# GrandPrIEEE.net
KiCad netlist of a schematic drawn in EAGLE
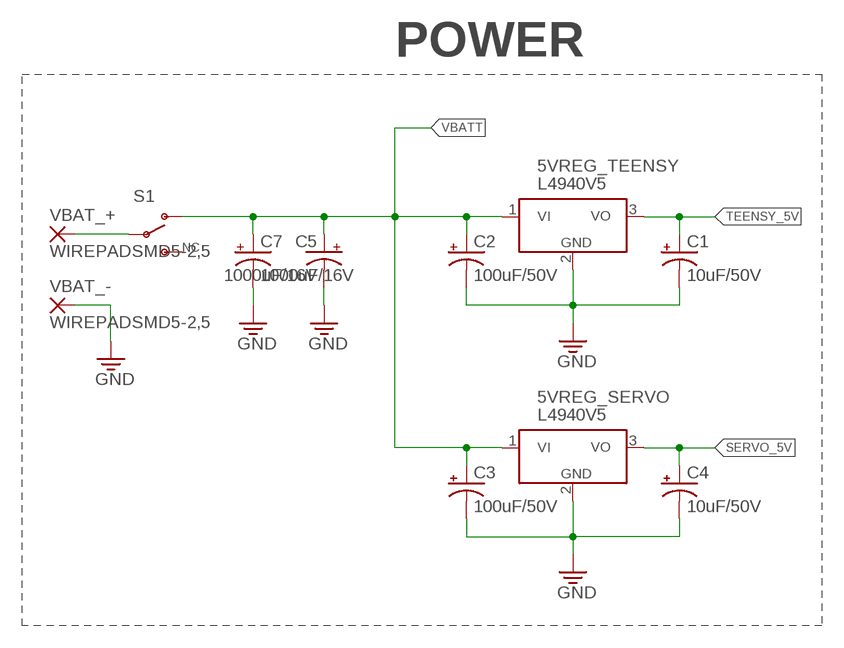
[diagram p0: schematic, sheet 1, part 1 of 2]
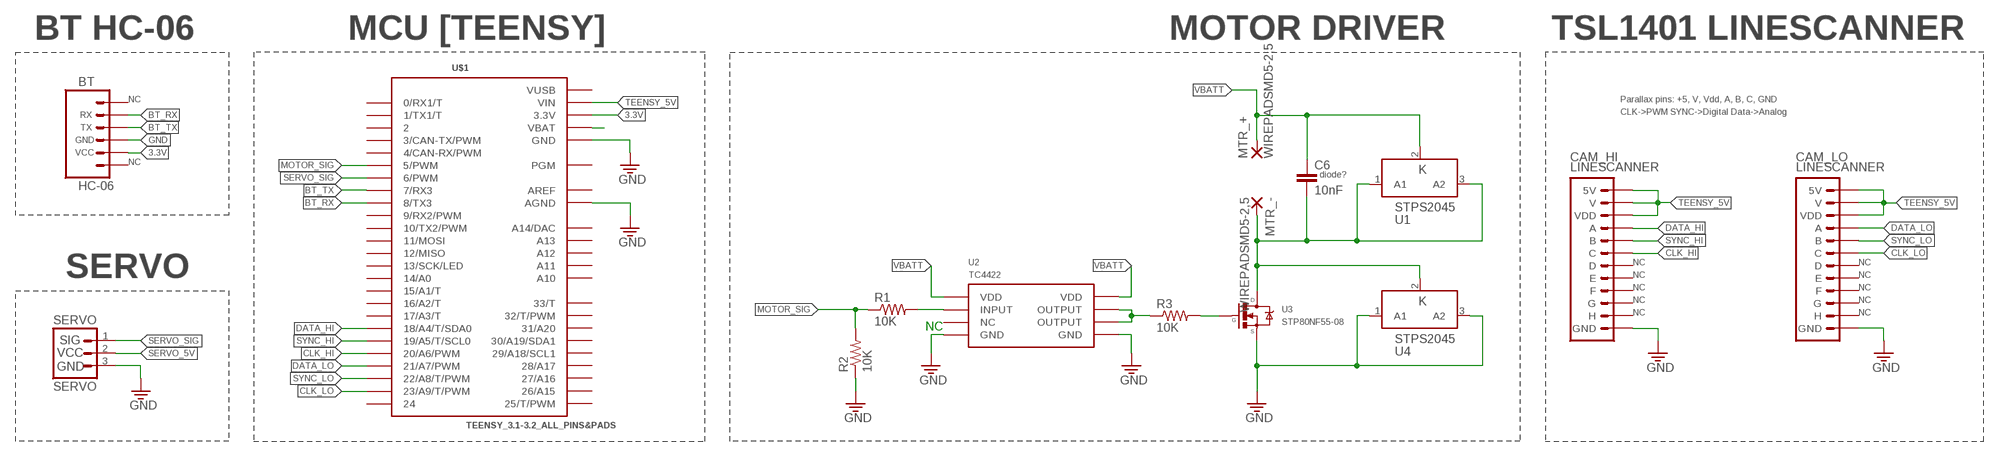
[diagram p1: schematic, sheet 1, part 2 of 2]

(export (version "E")
  (design (tool "Eeschema 10.0.6"))
  (components
    (comp (ref "5VREG_SERVO")
      (value "L4940V5")
      (footprint "eagle-import:TO-220-HEATSINK")
      (libsource (lib "eagle-import") (part "L4940V5_HEATSINK"))
    )
    (comp (ref "5VREG_TEENSY")
      (value "L4940V5")
      (footprint "eagle-import:TO-220-HEATSINK")
      (libsource (lib "eagle-import") (part "L4940V5_HEATSINK"))
    )
    (comp (ref "BT")
      (value "HC-06")
      (footprint "eagle-import:1X06")
      (libsource (lib "eagle-import") (part "HC-06"))
    )
    (comp (ref "C1")
      (value "10uF/50V")
      (footprint "eagle-import:E2,5-5")
      (libsource (lib "eagle-import") (part "CPOL-USE2.5-5"))
    )
    (comp (ref "C2")
      (value "100uF/50V")
      (footprint "eagle-import:E3,5-8")
      (libsource (lib "eagle-import") (part "CPOL-USE3.5-8"))
    )
    (comp (ref "C3")
      (value "100uF/50V")
      (footprint "eagle-import:E3,5-8")
      (libsource (lib "eagle-import") (part "CPOL-USE3.5-8"))
    )
    (comp (ref "C4")
      (value "10uF/50V")
      (footprint "eagle-import:E2,5-5")
      (libsource (lib "eagle-import") (part "CPOL-USE2.5-5"))
    )
    (comp (ref "C5")
      (value "1000uF/16V")
      (footprint "eagle-import:E5-10,5")
      (libsource (lib "eagle-import") (part "CPOL-USE5-10.5"))
    )
    (comp (ref "C6")
      (value "10nF")
      (footprint "eagle-import:C025-025X050")
      (libsource (lib "eagle-import") (part "C-EU025-025X050"))
    )
    (comp (ref "C7")
      (value "1000uF/16V")
      (footprint "eagle-import:E5-10,5")
      (libsource (lib "eagle-import") (part "CPOL-USE5-10.5"))
    )
    (comp (ref "CAM_HI")
      (value "LINESCANNER")
      (footprint "eagle-import:LINESCANNER")
      (libsource (lib "eagle-import") (part "LINESCANNER"))
    )
    (comp (ref "CAM_LO")
      (value "LINESCANNER")
      (footprint "eagle-import:LINESCANNER")
      (libsource (lib "eagle-import") (part "LINESCANNER"))
    )
    (comp (ref "MTR_+")
      (value "WIREPADSMD5-2,5")
      (footprint "eagle-import:5-2,5")
      (libsource (lib "eagle-import") (part "WIREPADSMD5-2,5"))
    )
    (comp (ref "MTR_-")
      (value "WIREPADSMD5-2,5")
      (footprint "eagle-import:5-2,5")
      (libsource (lib "eagle-import") (part "WIREPADSMD5-2,5"))
    )
    (comp (ref "R1")
      (value "10K")
      (footprint "eagle-import:0207_7")
      (libsource (lib "eagle-import") (part "R-US_0207/7"))
    )
    (comp (ref "R2")
      (value "10K")
      (footprint "eagle-import:0207_7")
      (libsource (lib "eagle-import") (part "R-US_0207/7"))
    )
    (comp (ref "R3")
      (value "10K")
      (footprint "eagle-import:0207_7")
      (libsource (lib "eagle-import") (part "R-US_0207/7"))
    )
    (comp (ref "S1")
      (value "SW_MTS-102C4")
      (footprint "eagle-import:MTS-102C4")
      (libsource (lib "eagle-import") (part "SW_MTS-102C4"))
    )
    (comp (ref "SERVO")
      (value "SERVO")
      (footprint "eagle-import:1X03")
      (libsource (lib "eagle-import") (part "SERVO"))
    )
    (comp (ref "U$1")
      (value "TEENSY_3.1-3.2_ALL_PINS&PADS")
      (footprint "eagle-import:TEENSY_3.0-3.2_ALL_PINS_&_PADS")
      (libsource (lib "eagle-import") (part "TEENSY_3.1-3.2_ALL_PINS&PADS"))
    )
    (comp (ref "U1")
      (value "STPS2045")
      (footprint "eagle-import:TO-220")
      (libsource (lib "eagle-import") (part "STPS2045"))
    )
    (comp (ref "U2")
      (value "TC4422")
      (footprint "eagle-import:DIP-8")
      (libsource (lib "eagle-import") (part "TC4422"))
    )
    (comp (ref "U3")
      (value "STP80NF55-08")
      (footprint "eagle-import:TO-220")
      (libsource (lib "eagle-import") (part "STP80NF55-08"))
    )
    (comp (ref "U4")
      (value "STPS2045")
      (footprint "eagle-import:TO-220")
      (libsource (lib "eagle-import") (part "STPS2045"))
    )
    (comp (ref "VBAT_+")
      (value "WIREPADSMD5-2,5")
      (footprint "eagle-import:5-2,5")
      (libsource (lib "eagle-import") (part "WIREPADSMD5-2,5"))
    )
    (comp (ref "VBAT_-")
      (value "WIREPADSMD5-2,5")
      (footprint "eagle-import:5-2,5")
      (libsource (lib "eagle-import") (part "WIREPADSMD5-2,5"))
    )
  )
  (nets
    (net (code "1") (name "/AREF") (class "Default")
      (node (ref "U$1") (pin "AREF") (pinfunction "AREF_AREF") (pintype "power_in"))
    )
    (net (code "2") (name "/VUSB") (class "Default")
      (node (ref "U$1") (pin "VUSB") (pinfunction "VUSB_VUSB") (pintype "power_in"))
    )
    (net (code "3") (name "3.3V") (class "Default")
      (node (ref "BT") (pin "5") (pinfunction "VCC_5") (pintype "bidirectional"))
      (node (ref "U$1") (pin "3.3V") (pinfunction "3.3V_3.3V") (pintype "power_in"))
      (node (ref "U$1") (pin "3.3V1") (pinfunction "3.3V_3.3V1") (pintype "power_in"))
      (node (ref "U$1") (pin "3.3V2") (pinfunction "3.3V_3.3V2") (pintype "power_in"))
    )
    (net (code "4") (name "BT_RX") (class "Default")
      (node (ref "BT") (pin "2") (pinfunction "RX_2") (pintype "bidirectional"))
      (node (ref "U$1") (pin "8") (pinfunction "8/TX3_8") (pintype "bidirectional"))
    )
    (net (code "5") (name "BT_TX") (class "Default")
      (node (ref "BT") (pin "3") (pinfunction "TX_3") (pintype "bidirectional"))
      (node (ref "U$1") (pin "7") (pinfunction "7/RX3_7") (pintype "bidirectional"))
    )
    (net (code "6") (name "CLK_HI") (class "Default")
      (node (ref "CAM_HI") (pin "6") (pinfunction "C_6") (pintype "bidirectional"))
      (node (ref "U$1") (pin "20/A6") (pinfunction "20/A6/PWM_20/A6") (pintype "bidirectional"))
    )
    (net (code "7") (name "CLK_LO") (class "Default")
      (node (ref "CAM_LO") (pin "6") (pinfunction "C_6") (pintype "bidirectional"))
      (node (ref "U$1") (pin "23/A9") (pinfunction "23/A9/T/PWM_23/A9") (pintype "bidirectional"))
    )
    (net (code "8") (name "DATA_HI") (class "Default")
      (node (ref "CAM_HI") (pin "4") (pinfunction "A_4") (pintype "bidirectional"))
      (node (ref "U$1") (pin "18/A4") (pinfunction "18/A4/T/SDA0_18/A4") (pintype "bidirectional"))
    )
    (net (code "9") (name "DATA_LO") (class "Default")
      (node (ref "CAM_LO") (pin "4") (pinfunction "A_4") (pintype "bidirectional"))
      (node (ref "U$1") (pin "21/A7") (pinfunction "21/A7/PWM_21/A7") (pintype "bidirectional"))
    )
    (net (code "10") (name "GND") (class "Default")
      (node (ref "5VREG_SERVO") (pin "2") (pinfunction "GND_2") (pintype "bidirectional"))
      (node (ref "5VREG_TEENSY") (pin "2") (pinfunction "GND_2") (pintype "bidirectional"))
      (node (ref "BT") (pin "4") (pinfunction "GND_4") (pintype "bidirectional"))
      (node (ref "C1") (pin "-") (pinfunction "-_-") (pintype "passive"))
      (node (ref "C2") (pin "-") (pinfunction "-_-") (pintype "passive"))
      (node (ref "C3") (pin "-") (pinfunction "-_-") (pintype "passive"))
      (node (ref "C4") (pin "-") (pinfunction "-_-") (pintype "passive"))
      (node (ref "C5") (pin "-") (pinfunction "-_-") (pintype "passive"))
      (node (ref "C7") (pin "-") (pinfunction "-_-") (pintype "passive"))
      (node (ref "CAM_HI") (pin "12") (pinfunction "GND_12") (pintype "bidirectional"))
      (node (ref "CAM_LO") (pin "12") (pinfunction "GND_12") (pintype "bidirectional"))
      (node (ref "R2") (pin "1") (pinfunction "1_1") (pintype "passive"))
      (node (ref "SERVO") (pin "3") (pinfunction "GND_3") (pintype "bidirectional"))
      (node (ref "U$1") (pin "AGND") (pinfunction "AGND_AGND") (pintype "power_in"))
      (node (ref "U$1") (pin "GND") (pinfunction "GND_GND") (pintype "power_in"))
      (node (ref "U$1") (pin "GND1") (pinfunction "GND_GND1") (pintype "power_in"))
      (node (ref "U$1") (pin "GND2") (pinfunction "GND_GND2") (pintype "power_in"))
      (node (ref "U2") (pin "4") (pinfunction "GND_4") (pintype "power_in"))
      (node (ref "U2") (pin "5") (pinfunction "GND_5") (pintype "power_in"))
      (node (ref "U3") (pin "3") (pinfunction "S_3") (pintype "bidirectional"))
      (node (ref "U4") (pin "1") (pinfunction "A1_1") (pintype "bidirectional"))
      (node (ref "U4") (pin "3") (pinfunction "A2_3") (pintype "bidirectional"))
      (node (ref "VBAT_-") (pin "1") (pinfunction "P_1") (pintype "passive"))
    )
    (net (code "11") (name "MOTOR_SIG") (class "Default")
      (node (ref "R1") (pin "1") (pinfunction "1_1") (pintype "passive"))
      (node (ref "R2") (pin "2") (pinfunction "2_2") (pintype "passive"))
      (node (ref "U$1") (pin "5") (pinfunction "5/PWM_5") (pintype "bidirectional"))
    )
    (net (code "12") (name "Net-(MTR_--P)") (class "Default")
      (node (ref "C6") (pin "2") (pinfunction "2_2") (pintype "passive"))
      (node (ref "MTR_-") (pin "1") (pinfunction "P_1") (pintype "passive"))
      (node (ref "U1") (pin "1") (pinfunction "A1_1") (pintype "bidirectional"))
      (node (ref "U1") (pin "3") (pinfunction "A2_3") (pintype "bidirectional"))
      (node (ref "U3") (pin "2") (pinfunction "D_2") (pintype "bidirectional"))
      (node (ref "U4") (pin "2") (pinfunction "K_2") (pintype "bidirectional"))
    )
    (net (code "13") (name "Net-(R3-Pad1)") (class "Default")
      (node (ref "R3") (pin "1") (pinfunction "1_1") (pintype "passive"))
      (node (ref "U2") (pin "6") (pinfunction "OUTPUT_6") (pintype "output"))
      (node (ref "U2") (pin "7") (pinfunction "OUTPUT_7") (pintype "output"))
    )
    (net (code "14") (name "Net-(U2-INPUT)") (class "Default")
      (node (ref "R1") (pin "2") (pinfunction "2_2") (pintype "passive"))
      (node (ref "U2") (pin "2") (pinfunction "INPUT_2") (pintype "input"))
    )
    (net (code "15") (name "Net-(U3-G)") (class "Default")
      (node (ref "R3") (pin "2") (pinfunction "2_2") (pintype "passive"))
      (node (ref "U3") (pin "1") (pinfunction "G_1") (pintype "bidirectional"))
    )
    (net (code "16") (name "Net-(VBAT_+-P)") (class "Default")
      (node (ref "S1") (pin "P") (pinfunction "P_P") (pintype "passive"))
      (node (ref "VBAT_+") (pin "1") (pinfunction "P_1") (pintype "passive"))
    )
    (net (code "17") (name "SERVO_5V") (class "Default")
      (node (ref "5VREG_SERVO") (pin "3") (pinfunction "VO_3") (pintype "bidirectional"))
      (node (ref "C4") (pin "+") (pinfunction "+_+") (pintype "passive"))
      (node (ref "SERVO") (pin "2") (pinfunction "VCC_2") (pintype "bidirectional"))
    )
    (net (code "18") (name "SERVO_SIG") (class "Default")
      (node (ref "SERVO") (pin "1") (pinfunction "SIG_1") (pintype "bidirectional"))
      (node (ref "U$1") (pin "6") (pinfunction "6/PWM_6") (pintype "bidirectional"))
    )
    (net (code "19") (name "SYNC_HI") (class "Default")
      (node (ref "CAM_HI") (pin "5") (pinfunction "B_5") (pintype "bidirectional"))
      (node (ref "U$1") (pin "19/A5") (pinfunction "19/A5/T/SCL0_19/A5") (pintype "bidirectional"))
    )
    (net (code "20") (name "SYNC_LO") (class "Default")
      (node (ref "CAM_LO") (pin "5") (pinfunction "B_5") (pintype "bidirectional"))
      (node (ref "U$1") (pin "22/A8") (pinfunction "22/A8/T/PWM_22/A8") (pintype "bidirectional"))
    )
    (net (code "21") (name "TEENSY_5V") (class "Default")
      (node (ref "5VREG_TEENSY") (pin "3") (pinfunction "VO_3") (pintype "bidirectional"))
      (node (ref "C1") (pin "+") (pinfunction "+_+") (pintype "passive"))
      (node (ref "CAM_HI") (pin "1") (pinfunction "5V_1") (pintype "bidirectional"))
      (node (ref "CAM_HI") (pin "2") (pinfunction "V_2") (pintype "bidirectional"))
      (node (ref "CAM_HI") (pin "3") (pinfunction "VDD_3") (pintype "bidirectional"))
      (node (ref "CAM_LO") (pin "1") (pinfunction "5V_1") (pintype "bidirectional"))
      (node (ref "CAM_LO") (pin "2") (pinfunction "V_2") (pintype "bidirectional"))
      (node (ref "CAM_LO") (pin "3") (pinfunction "VDD_3") (pintype "bidirectional"))
      (node (ref "U$1") (pin "VIN") (pinfunction "VIN_VIN") (pintype "power_in"))
    )
    (net (code "22") (name "VBATT") (class "Default")
      (node (ref "5VREG_SERVO") (pin "1") (pinfunction "VI_1") (pintype "bidirectional"))
      (node (ref "5VREG_TEENSY") (pin "1") (pinfunction "VI_1") (pintype "bidirectional"))
      (node (ref "C2") (pin "+") (pinfunction "+_+") (pintype "passive"))
      (node (ref "C3") (pin "+") (pinfunction "+_+") (pintype "passive"))
      (node (ref "C5") (pin "+") (pinfunction "+_+") (pintype "passive"))
      (node (ref "C6") (pin "1") (pinfunction "1_1") (pintype "passive"))
      (node (ref "C7") (pin "+") (pinfunction "+_+") (pintype "passive"))
      (node (ref "MTR_+") (pin "1") (pinfunction "P_1") (pintype "passive"))
      (node (ref "S1") (pin "T2") (pinfunction "T2_T2") (pintype "passive"))
      (node (ref "U1") (pin "2") (pinfunction "K_2") (pintype "bidirectional"))
      (node (ref "U2") (pin "1") (pinfunction "VDD_1") (pintype "power_in"))
      (node (ref "U2") (pin "8") (pinfunction "VDD_8") (pintype "power_in"))
    )
    (net (code "23") (name "unconnected-(BT-EN-Pad6)") (class "Default")
      (node (ref "BT") (pin "6") (pinfunction "EN_6") (pintype "no_connect"))
    )
    (net (code "24") (name "unconnected-(BT-STATE-Pad1)") (class "Default")
      (node (ref "BT") (pin "1") (pinfunction "STATE_1") (pintype "no_connect"))
    )
    (net (code "25") (name "unconnected-(CAM_HI-D-Pad7)") (class "Default")
      (node (ref "CAM_HI") (pin "7") (pinfunction "D_7") (pintype "bidirectional"))
    )
    (net (code "26") (name "unconnected-(CAM_HI-E-Pad8)") (class "Default")
      (node (ref "CAM_HI") (pin "8") (pinfunction "E_8") (pintype "bidirectional"))
    )
    (net (code "27") (name "unconnected-(CAM_HI-F-Pad9)") (class "Default")
      (node (ref "CAM_HI") (pin "9") (pinfunction "F_9") (pintype "bidirectional"))
    )
    (net (code "28") (name "unconnected-(CAM_HI-G-Pad10)") (class "Default")
      (node (ref "CAM_HI") (pin "10") (pinfunction "G_10") (pintype "bidirectional"))
    )
    (net (code "29") (name "unconnected-(CAM_HI-H-Pad11)") (class "Default")
      (node (ref "CAM_HI") (pin "11") (pinfunction "H_11") (pintype "bidirectional"))
    )
    (net (code "30") (name "unconnected-(CAM_LO-D-Pad7)") (class "Default")
      (node (ref "CAM_LO") (pin "7") (pinfunction "D_7") (pintype "bidirectional"))
    )
    (net (code "31") (name "unconnected-(CAM_LO-E-Pad8)") (class "Default")
      (node (ref "CAM_LO") (pin "8") (pinfunction "E_8") (pintype "bidirectional"))
    )
    (net (code "32") (name "unconnected-(CAM_LO-F-Pad9)") (class "Default")
      (node (ref "CAM_LO") (pin "9") (pinfunction "F_9") (pintype "bidirectional"))
    )
    (net (code "33") (name "unconnected-(CAM_LO-G-Pad10)") (class "Default")
      (node (ref "CAM_LO") (pin "10") (pinfunction "G_10") (pintype "bidirectional"))
    )
    (net (code "34") (name "unconnected-(CAM_LO-H-Pad11)") (class "Default")
      (node (ref "CAM_LO") (pin "11") (pinfunction "H_11") (pintype "bidirectional"))
    )
    (net (code "35") (name "unconnected-(S1-PadT1)") (class "Default")
      (node (ref "S1") (pin "T1") (pinfunction "T1_T1") (pintype "passive"))
    )
    (net (code "36") (name "unconnected-(U$1-0{slash}RX1{slash}T-Pad0)") (class "Default")
      (node (ref "U$1") (pin "0") (pinfunction "0/RX1/T_0") (pintype "bidirectional"))
    )
    (net (code "37") (name "unconnected-(U$1-1{slash}TX1{slash}T-Pad1)") (class "Default")
      (node (ref "U$1") (pin "1") (pinfunction "1/TX1/T_1") (pintype "bidirectional"))
    )
    (net (code "38") (name "unconnected-(U$1-3{slash}CAN-TX{slash}PWM-Pad3)") (class "Default")
      (node (ref "U$1") (pin "3") (pinfunction "3/CAN-TX/PWM_3") (pintype "bidirectional"))
    )
    (net (code "39") (name "unconnected-(U$1-4{slash}CAN-RX{slash}PWM-Pad4)") (class "Default")
      (node (ref "U$1") (pin "4") (pinfunction "4/CAN-RX/PWM_4") (pintype "bidirectional"))
    )
    (net (code "40") (name "unconnected-(U$1-9{slash}RX2{slash}PWM-Pad9)") (class "Default")
      (node (ref "U$1") (pin "9") (pinfunction "9/RX2/PWM_9") (pintype "bidirectional"))
    )
    (net (code "41") (name "unconnected-(U$1-10{slash}TX2{slash}PWM-Pad10)") (class "Default")
      (node (ref "U$1") (pin "10") (pinfunction "10/TX2/PWM_10") (pintype "bidirectional"))
    )
    (net (code "42") (name "unconnected-(U$1-11{slash}MOSI-Pad11)") (class "Default")
      (node (ref "U$1") (pin "11") (pinfunction "11/MOSI_11") (pintype "bidirectional"))
    )
    (net (code "43") (name "unconnected-(U$1-12{slash}MISO-Pad12)") (class "Default")
      (node (ref "U$1") (pin "12") (pinfunction "12/MISO_12") (pintype "bidirectional"))
    )
    (net (code "44") (name "unconnected-(U$1-13{slash}SCK{slash}LED-Pad13)") (class "Default")
      (node (ref "U$1") (pin "13") (pinfunction "13/SCK/LED_13") (pintype "bidirectional"))
    )
    (net (code "45") (name "unconnected-(U$1-15{slash}A1{slash}T-Pad15{slash}A1)") (class "Default")
      (node (ref "U$1") (pin "15/A1") (pinfunction "15/A1/T_15/A1") (pintype "bidirectional"))
    )
    (net (code "46") (name "unconnected-(U$1-16{slash}A2{slash}T-Pad16{slash}A2)") (class "Default")
      (node (ref "U$1") (pin "16/A2") (pinfunction "16/A2/T_16/A2") (pintype "bidirectional"))
    )
    (net (code "47") (name "unconnected-(U$1-17{slash}A3{slash}T-Pad17{slash}A3)") (class "Default")
      (node (ref "U$1") (pin "17/A3") (pinfunction "17/A3/T_17/A3") (pintype "bidirectional"))
    )
    (net (code "48") (name "unconnected-(U$1-25{slash}T{slash}PWM-Pad25)") (class "Default")
      (node (ref "U$1") (pin "25") (pinfunction "25/T/PWM_25") (pintype "bidirectional"))
    )
    (net (code "49") (name "unconnected-(U$1-26{slash}A15-Pad26)") (class "Default")
      (node (ref "U$1") (pin "26") (pinfunction "26/A15_26") (pintype "bidirectional"))
    )
    (net (code "50") (name "unconnected-(U$1-27{slash}A16-Pad27)") (class "Default")
      (node (ref "U$1") (pin "27") (pinfunction "27/A16_27") (pintype "bidirectional"))
    )
    (net (code "51") (name "unconnected-(U$1-28{slash}A17-Pad28)") (class "Default")
      (node (ref "U$1") (pin "28") (pinfunction "28/A17_28") (pintype "bidirectional"))
    )
    (net (code "52") (name "unconnected-(U$1-29{slash}A18{slash}SCL1-Pad29)") (class "Default")
      (node (ref "U$1") (pin "29") (pinfunction "29/A18/SCL1_29") (pintype "bidirectional"))
    )
    (net (code "53") (name "unconnected-(U$1-30{slash}A19{slash}SDA1-Pad30)") (class "Default")
      (node (ref "U$1") (pin "30") (pinfunction "30/A19/SDA1_30") (pintype "bidirectional"))
    )
    (net (code "54") (name "unconnected-(U$1-31{slash}A20-Pad31)") (class "Default")
      (node (ref "U$1") (pin "31") (pinfunction "31/A20_31") (pintype "bidirectional"))
    )
    (net (code "55") (name "unconnected-(U$1-32{slash}T{slash}PWM-Pad32)") (class "Default")
      (node (ref "U$1") (pin "32") (pinfunction "32/T/PWM_32") (pintype "bidirectional"))
    )
    (net (code "56") (name "unconnected-(U$1-33{slash}T-Pad33)") (class "Default")
      (node (ref "U$1") (pin "33") (pinfunction "33/T_33") (pintype "bidirectional"))
    )
    (net (code "57") (name "unconnected-(U$1-A14{slash}DAC-PadRESET{slash}DAC)") (class "Default")
      (node (ref "U$1") (pin "RESET/DAC") (pinfunction "A14/DAC_RESET/DAC") (pintype "bidirectional"))
    )
    (net (code "58") (name "unconnected-(U$1-Pad2)") (class "Default")
      (node (ref "U$1") (pin "2") (pinfunction "2_2") (pintype "bidirectional"))
    )
    (net (code "59") (name "unconnected-(U$1-Pad14{slash}A0)") (class "Default")
      (node (ref "U$1") (pin "14/A0") (pinfunction "14/A0_14/A0") (pintype "bidirectional"))
    )
    (net (code "60") (name "unconnected-(U$1-Pad24)") (class "Default")
      (node (ref "U$1") (pin "24") (pinfunction "24_24") (pintype "bidirectional"))
    )
    (net (code "61") (name "unconnected-(U$1-PadA10)") (class "Default")
      (node (ref "U$1") (pin "A10") (pinfunction "A10_A10") (pintype "bidirectional"))
    )
    (net (code "62") (name "unconnected-(U$1-PadA11)") (class "Default")
      (node (ref "U$1") (pin "A11") (pinfunction "A11_A11") (pintype "bidirectional"))
    )
    (net (code "63") (name "unconnected-(U$1-PadA12)") (class "Default")
      (node (ref "U$1") (pin "A12") (pinfunction "A12_A12") (pintype "bidirectional"))
    )
    (net (code "64") (name "unconnected-(U$1-PadA13)") (class "Default")
      (node (ref "U$1") (pin "A13") (pinfunction "A13_A13") (pintype "bidirectional"))
    )
    (net (code "65") (name "unconnected-(U$1-PadPGM)") (class "Default")
      (node (ref "U$1") (pin "PGM") (pinfunction "PGM_PGM") (pintype "bidirectional"))
    )
    (net (code "66") (name "unconnected-(U$1-PadVBAT)") (class "Default")
      (node (ref "U$1") (pin "VBAT") (pinfunction "VBAT_VBAT") (pintype "power_in"))
    )
    (net (code "67") (name "unconnected-(U2-NC-Pad3)") (class "Default")
      (node (ref "U2") (pin "3") (pinfunction "NC_3") (pintype "no_connect"))
    )
  )
)
